# Aircondition.net
KiCad netlist of a schematic drawn in EAGLE
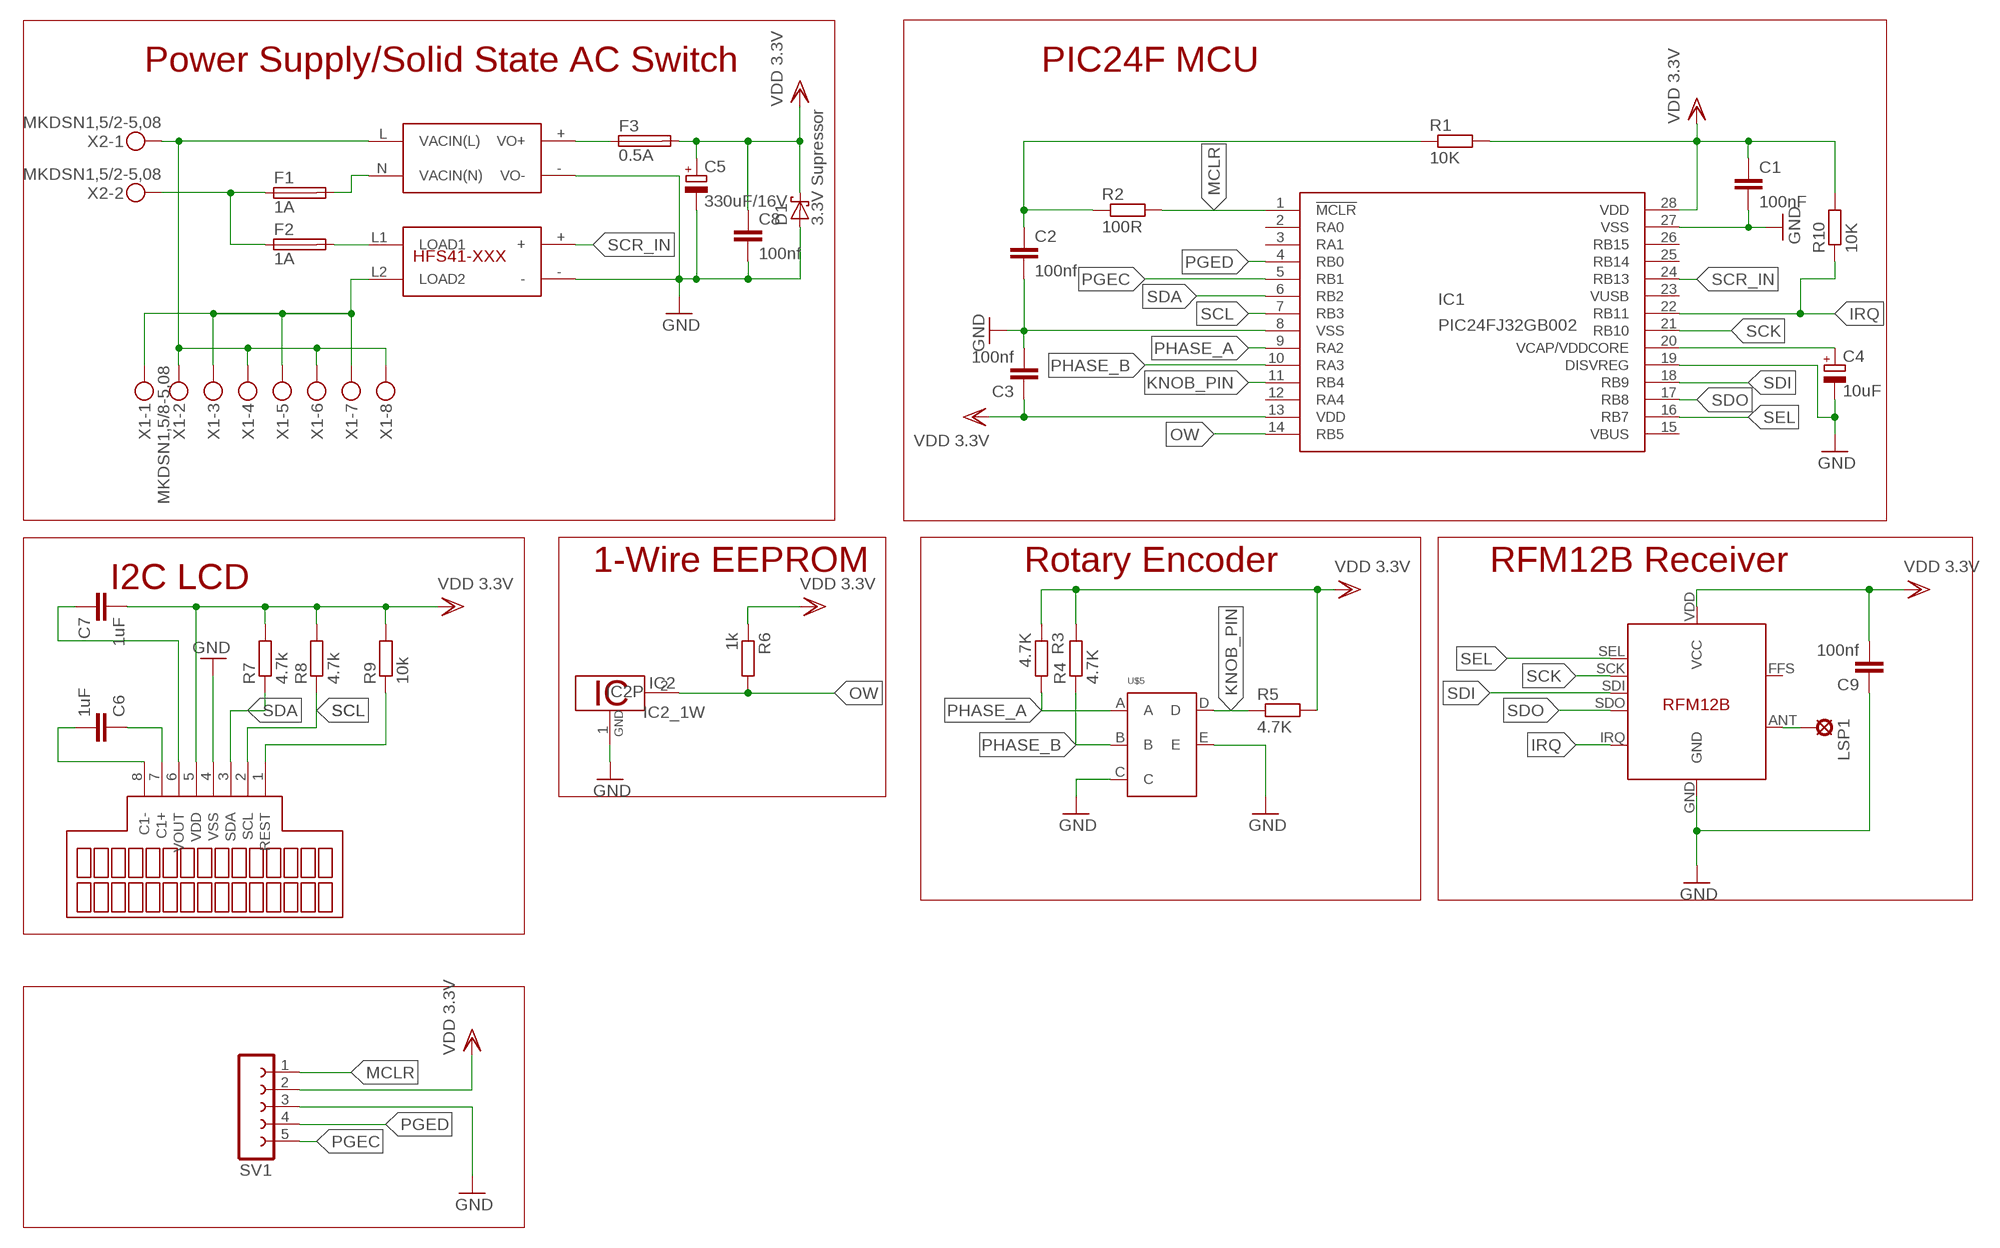
[diagram p0: schematic, sheet 1]

(export (version "E")
  (design (tool "Eeschema 10.0.6"))
  (components
    (comp (ref "C1")
      (value "100nF")
      (footprint "eagle-import:C025-025X050")
      (libsource (lib "eagle-import") (part "C-EU025-025X050"))
    )
    (comp (ref "C2")
      (value "100nf")
      (footprint "eagle-import:C025-025X050")
      (libsource (lib "eagle-import") (part "C-EU025-025X050"))
    )
    (comp (ref "C3")
      (value "100nf")
      (footprint "eagle-import:C102-043X133")
      (libsource (lib "eagle-import") (part "C-EU102-043X133"))
    )
    (comp (ref "C4")
      (value "10uF")
      (footprint "eagle-import:E5-5")
      (libsource (lib "eagle-import") (part "CPOL-EUE5-5"))
    )
    (comp (ref "C5")
      (value "330uF/16V")
      (footprint "eagle-import:E5-10,5")
      (libsource (lib "eagle-import") (part "CPOL-EUE5-10.5"))
    )
    (comp (ref "C6")
      (value "1uF")
      (footprint "eagle-import:C025-025X050")
      (libsource (lib "eagle-import") (part "C-EU025-025X050"))
    )
    (comp (ref "C7")
      (value "1uF")
      (footprint "eagle-import:C025-025X050")
      (libsource (lib "eagle-import") (part "C-EU025-025X050"))
    )
    (comp (ref "C8")
      (value "100nf")
      (footprint "eagle-import:C025-025X050")
      (libsource (lib "eagle-import") (part "C-EU025-025X050"))
    )
    (comp (ref "C9")
      (value "100nf")
      (footprint "eagle-import:C102-043X133")
      (libsource (lib "eagle-import") (part "C-EU102-043X133"))
    )
    (comp (ref "D1")
      (value "3.3V Supressor")
      (footprint "eagle-import:C4111-15")
      (libsource (lib "eagle-import") (part "ICTE5"))
    )
    (comp (ref "F1")
      (value "1A")
      (footprint "eagle-import:SH22,5A")
      (libsource (lib "eagle-import") (part "FUSESH22,5A"))
    )
    (comp (ref "F2")
      (value "1A")
      (footprint "eagle-import:SH22,5A")
      (libsource (lib "eagle-import") (part "FUSESH22,5A"))
    )
    (comp (ref "F3")
      (value "0.5A")
      (footprint "eagle-import:SH22,5A")
      (libsource (lib "eagle-import") (part "FUSESH22,5A"))
    )
    (comp (ref "IC1")
      (value "PIC24FJ32GB002")
      (footprint "eagle-import:DIL28-3")
      (libsource (lib "eagle-import") (part "PIC24FJ32GB002"))
    )
    (comp (ref "IC2")
      (value "DS2431")
      (footprint "eagle-import:TO92-")
      (libsource (lib "eagle-import") (part "DS2431"))
    )
    (comp (ref "LSP1")
      (value "ANT")
      (footprint "eagle-import:LSP10")
      (libsource (lib "eagle-import") (part "LSP10"))
    )
    (comp (ref "R1")
      (value "10K")
      (footprint "eagle-import:0204_5")
      (libsource (lib "eagle-import") (part "R-EU_0204/5"))
    )
    (comp (ref "R2")
      (value "100R")
      (footprint "eagle-import:0204_5")
      (libsource (lib "eagle-import") (part "R-EU_0204/5"))
    )
    (comp (ref "R3")
      (value "4.7K")
      (footprint "eagle-import:0204_7")
      (libsource (lib "eagle-import") (part "R-EU_0204/7"))
    )
    (comp (ref "R4")
      (value "4.7K")
      (footprint "eagle-import:0204_7")
      (libsource (lib "eagle-import") (part "R-EU_0204/7"))
    )
    (comp (ref "R5")
      (value "4.7K")
      (footprint "eagle-import:0204_7")
      (libsource (lib "eagle-import") (part "R-EU_0204/7"))
    )
    (comp (ref "R6")
      (value "1k")
      (footprint "eagle-import:0207_2V")
      (libsource (lib "eagle-import") (part "R-EU_0207/2V"))
    )
    (comp (ref "R7")
      (value "4.7k")
      (footprint "eagle-import:0204_5")
      (libsource (lib "eagle-import") (part "R-EU_0204/5"))
    )
    (comp (ref "R8")
      (value "4.7k")
      (footprint "eagle-import:0204_5")
      (libsource (lib "eagle-import") (part "R-EU_0204/5"))
    )
    (comp (ref "R9")
      (value "10k")
      (footprint "eagle-import:0204_5")
      (libsource (lib "eagle-import") (part "R-EU_0204/5"))
    )
    (comp (ref "R10")
      (value "10K")
      (footprint "eagle-import:0207_10")
      (libsource (lib "eagle-import") (part "R-EU_0207/10"))
    )
    (comp (ref "SV1")
      (value "FE05-1")
      (footprint "eagle-import:FE05-1")
      (libsource (lib "eagle-import") (part "FE05-1"))
    )
    (comp (ref "U$1")
      (value "RAC01-3.3SC")
      (footprint "eagle-import:RAC01-XXSC")
      (libsource (lib "eagle-import") (part "RAC01-3.3SCSTANDARD"))
    )
    (comp (ref "U$2")
      (value "HFS41D-240A5Z-NGSTANDARD")
      (footprint "eagle-import:HFS41-EXPOXY-RESIN")
      (libsource (lib "eagle-import") (part "HFS41D-240A5Z-NGSTANDARD"))
    )
    (comp (ref "U$3")
      (value "NHD-C0216CIZ-FN-FBW-3VSIL8-2.54")
      (footprint "eagle-import:SIL8-2.54")
      (libsource (lib "eagle-import") (part "NHD-C0216CIZ-FN-FBW-3VSIL8-2.54"))
    )
    (comp (ref "U$4")
      (value "RFM12B")
      (footprint "eagle-import:RFM12B")
      (libsource (lib "eagle-import") (part "RFM12B"))
    )
    (comp (ref "U$5")
      (value "ENCODER-E")
      (footprint "eagle-import:ENCODER")
      (libsource (lib "eagle-import") (part "ENCODER-E"))
    )
    (comp (ref "X1")
      (value "MKDSN1,5/8-5,08")
      (footprint "eagle-import:MKDSN1,5_8-5,08")
      (libsource (lib "eagle-import") (part "MKDSN1,5/8-5,08"))
    )
    (comp (ref "X2")
      (value "MKDSN1,5/2-5,08")
      (footprint "eagle-import:MKDSN1,5_2-5,08")
      (libsource (lib "eagle-import") (part "MKDSN1,5/2-5,08"))
    )
  )
  (nets
    (net (code "1") (name "GND") (class "Default")
      (node (ref "C1") (pin "2") (pinfunction "2_2") (pintype "passive"))
      (node (ref "C2") (pin "2") (pinfunction "2_2") (pintype "passive"))
      (node (ref "C3") (pin "2") (pinfunction "2_2") (pintype "passive"))
      (node (ref "C4") (pin "-") (pinfunction "-_-") (pintype "passive"))
      (node (ref "C5") (pin "-") (pinfunction "-_-") (pintype "passive"))
      (node (ref "C8") (pin "2") (pinfunction "2_2") (pintype "passive"))
      (node (ref "C9") (pin "1") (pinfunction "1_1") (pintype "passive"))
      (node (ref "D1") (pin "A") (pinfunction "A_A") (pintype "passive"))
      (node (ref "IC1") (pin "19") (pinfunction "DISVREG_19") (pintype "passive"))
      (node (ref "IC1") (pin "27") (pinfunction "VSS_27") (pintype "power_in"))
      (node (ref "IC1") (pin "8") (pinfunction "VSS_8") (pintype "power_in"))
      (node (ref "IC2") (pin "1") (pinfunction "GND_1") (pintype "power_in"))
      (node (ref "SV1") (pin "3") (pinfunction "3_3") (pintype "passive"))
      (node (ref "U$1") (pin "-") (pinfunction "VO-_-") (pintype "power_in"))
      (node (ref "U$2") (pin "-") (pinfunction "-_-") (pintype "bidirectional"))
      (node (ref "U$3") (pin "4") (pinfunction "VSS_4") (pintype "power_in"))
      (node (ref "U$4") (pin "GND") (pinfunction "GND_GND") (pintype "power_in"))
      (node (ref "U$5") (pin "C") (pinfunction "C_C") (pintype "power_in"))
      (node (ref "U$5") (pin "E") (pinfunction "E_E") (pintype "power_in"))
    )
    (net (code "2") (name "IRQ") (class "Default")
      (node (ref "IC1") (pin "22") (pinfunction "RB11_22") (pintype "input"))
      (node (ref "R10") (pin "1") (pinfunction "1_1") (pintype "passive"))
      (node (ref "U$4") (pin "IRQ") (pinfunction "IRQ_IRQ") (pintype "open_collector"))
    )
    (net (code "3") (name "KNOB_PIN") (class "Default")
      (node (ref "IC1") (pin "11") (pinfunction "RB4_11") (pintype "bidirectional"))
      (node (ref "R5") (pin "1") (pinfunction "1_1") (pintype "passive"))
      (node (ref "U$5") (pin "D") (pinfunction "D_D") (pintype "output"))
    )
    (net (code "4") (name "MCLR") (class "Default")
      (node (ref "IC1") (pin "1") (pinfunction "~{MCLR}_1") (pintype "bidirectional"))
      (node (ref "R2") (pin "2") (pinfunction "2_2") (pintype "passive"))
      (node (ref "SV1") (pin "1") (pinfunction "1_1") (pintype "passive"))
    )
    (net (code "5") (name "Net-(C2-Pad1)") (class "Default")
      (node (ref "C2") (pin "1") (pinfunction "1_1") (pintype "passive"))
      (node (ref "R1") (pin "1") (pinfunction "1_1") (pintype "passive"))
      (node (ref "R2") (pin "1") (pinfunction "1_1") (pintype "passive"))
    )
    (net (code "6") (name "Net-(IC1-VCAP{slash}VDDCORE)") (class "Default")
      (node (ref "C4") (pin "+") (pinfunction "+_+") (pintype "passive"))
      (node (ref "IC1") (pin "20") (pinfunction "VCAP/VDDCORE_20") (pintype "power_in"))
    )
    (net (code "7") (name "Net-(LSP1-PadMP)") (class "Default")
      (node (ref "LSP1") (pin "MP") (pinfunction "MP_MP") (pintype "passive"))
      (node (ref "U$4") (pin "ANT") (pinfunction "ANT_ANT") (pintype "passive"))
    )
    (net (code "8") (name "Net-(U$1-VACIN(L))") (class "Default")
      (node (ref "U$1") (pin "L") (pinfunction "VACIN(L)_L") (pintype "power_in"))
      (node (ref "X1") (pin "2") (pinfunction "KL_2") (pintype "passive"))
      (node (ref "X1") (pin "4") (pinfunction "KL_4") (pintype "passive"))
      (node (ref "X1") (pin "6") (pinfunction "KL_6") (pintype "passive"))
      (node (ref "X1") (pin "8") (pinfunction "KL_8") (pintype "passive"))
      (node (ref "X2") (pin "1") (pinfunction "KL_1") (pintype "passive"))
    )
    (net (code "9") (name "Net-(U$1-VACIN(N))") (class "Default")
      (node (ref "F1") (pin "2") (pinfunction "2_2") (pintype "passive"))
      (node (ref "U$1") (pin "N") (pinfunction "VACIN(N)_N") (pintype "power_in"))
    )
    (net (code "10") (name "Net-(U$1-VO+)") (class "Default")
      (node (ref "F3") (pin "1") (pinfunction "1_1") (pintype "passive"))
      (node (ref "U$1") (pin "+") (pinfunction "VO+_+") (pintype "power_in"))
    )
    (net (code "11") (name "Net-(U$2-LOAD1)") (class "Default")
      (node (ref "F2") (pin "2") (pinfunction "2_2") (pintype "passive"))
      (node (ref "U$2") (pin "L1") (pinfunction "LOAD1_L1") (pintype "bidirectional"))
    )
    (net (code "12") (name "Net-(U$2-LOAD2)") (class "Default")
      (node (ref "U$2") (pin "L2") (pinfunction "LOAD2_L2") (pintype "bidirectional"))
      (node (ref "X1") (pin "1") (pinfunction "KL_1") (pintype "passive"))
      (node (ref "X1") (pin "3") (pinfunction "KL_3") (pintype "passive"))
      (node (ref "X1") (pin "5") (pinfunction "KL_5") (pintype "passive"))
      (node (ref "X1") (pin "7") (pinfunction "KL_7") (pintype "passive"))
    )
    (net (code "13") (name "Net-(U$3-C1+)") (class "Default")
      (node (ref "C6") (pin "1") (pinfunction "1_1") (pintype "passive"))
      (node (ref "U$3") (pin "7") (pinfunction "C1+_7") (pintype "bidirectional"))
    )
    (net (code "14") (name "Net-(U$3-C1-)") (class "Default")
      (node (ref "C6") (pin "2") (pinfunction "2_2") (pintype "passive"))
      (node (ref "U$3") (pin "8") (pinfunction "C1-_8") (pintype "bidirectional"))
    )
    (net (code "15") (name "Net-(U$3-REST)") (class "Default")
      (node (ref "R9") (pin "1") (pinfunction "1_1") (pintype "passive"))
      (node (ref "U$3") (pin "1") (pinfunction "REST_1") (pintype "bidirectional"))
    )
    (net (code "16") (name "Net-(U$3-VOUT)") (class "Default")
      (node (ref "C7") (pin "1") (pinfunction "1_1") (pintype "passive"))
      (node (ref "U$3") (pin "6") (pinfunction "VOUT_6") (pintype "output"))
    )
    (net (code "17") (name "Net-(X2B-KL)") (class "Default")
      (node (ref "F1") (pin "1") (pinfunction "1_1") (pintype "passive"))
      (node (ref "F2") (pin "1") (pinfunction "1_1") (pintype "passive"))
      (node (ref "X2") (pin "2") (pinfunction "KL_2") (pintype "passive"))
    )
    (net (code "18") (name "OW") (class "Default")
      (node (ref "IC1") (pin "14") (pinfunction "RB5_14") (pintype "bidirectional"))
      (node (ref "IC2") (pin "2") (pinfunction "1W_2") (pintype "power_in"))
      (node (ref "R6") (pin "2") (pinfunction "2_2") (pintype "passive"))
    )
    (net (code "19") (name "PGEC") (class "Default")
      (node (ref "IC1") (pin "5") (pinfunction "RB1_5") (pintype "bidirectional"))
      (node (ref "SV1") (pin "5") (pinfunction "5_5") (pintype "passive"))
    )
    (net (code "20") (name "PGED") (class "Default")
      (node (ref "IC1") (pin "4") (pinfunction "RB0_4") (pintype "bidirectional"))
      (node (ref "SV1") (pin "4") (pinfunction "4_4") (pintype "passive"))
    )
    (net (code "21") (name "PHASE_A") (class "Default")
      (node (ref "IC1") (pin "9") (pinfunction "RA2_9") (pintype "bidirectional"))
      (node (ref "R3") (pin "2") (pinfunction "2_2") (pintype "passive"))
      (node (ref "U$5") (pin "A") (pinfunction "A_A") (pintype "output"))
    )
    (net (code "22") (name "PHASE_B") (class "Default")
      (node (ref "IC1") (pin "10") (pinfunction "RA3_10") (pintype "bidirectional"))
      (node (ref "R4") (pin "1") (pinfunction "1_1") (pintype "passive"))
      (node (ref "U$5") (pin "B") (pinfunction "B_B") (pintype "output"))
    )
    (net (code "23") (name "SCK") (class "Default")
      (node (ref "IC1") (pin "21") (pinfunction "RB10_21") (pintype "input"))
      (node (ref "U$4") (pin "SCK") (pinfunction "SCK_SCK") (pintype "input"))
    )
    (net (code "24") (name "SCL") (class "Default")
      (node (ref "IC1") (pin "7") (pinfunction "RB3_7") (pintype "bidirectional"))
      (node (ref "R8") (pin "1") (pinfunction "1_1") (pintype "passive"))
      (node (ref "U$3") (pin "2") (pinfunction "SCL_2") (pintype "bidirectional"))
    )
    (net (code "25") (name "SCR_IN") (class "Default")
      (node (ref "IC1") (pin "24") (pinfunction "RB13_24") (pintype "bidirectional"))
      (node (ref "U$2") (pin "+") (pinfunction "+_+") (pintype "input"))
    )
    (net (code "26") (name "SDA") (class "Default")
      (node (ref "IC1") (pin "6") (pinfunction "RB2_6") (pintype "bidirectional"))
      (node (ref "R7") (pin "1") (pinfunction "1_1") (pintype "passive"))
      (node (ref "U$3") (pin "3") (pinfunction "SDA_3") (pintype "bidirectional"))
    )
    (net (code "27") (name "SDI") (class "Default")
      (node (ref "IC1") (pin "18") (pinfunction "RB9_18") (pintype "output"))
      (node (ref "U$4") (pin "SDI") (pinfunction "SDI_SDI") (pintype "input"))
    )
    (net (code "28") (name "SDO") (class "Default")
      (node (ref "IC1") (pin "17") (pinfunction "RB8_17") (pintype "input"))
      (node (ref "U$4") (pin "SDO") (pinfunction "SDO_SDO") (pintype "output"))
    )
    (net (code "29") (name "SEL") (class "Default")
      (node (ref "IC1") (pin "16") (pinfunction "RB7_16") (pintype "bidirectional"))
      (node (ref "U$4") (pin "SEL") (pinfunction "SEL_SEL") (pintype "input"))
    )
    (net (code "30") (name "VDD 3.3V") (class "Default")
      (node (ref "C1") (pin "1") (pinfunction "1_1") (pintype "passive"))
      (node (ref "C3") (pin "1") (pinfunction "1_1") (pintype "passive"))
      (node (ref "C5") (pin "+") (pinfunction "+_+") (pintype "passive"))
      (node (ref "C7") (pin "2") (pinfunction "2_2") (pintype "passive"))
      (node (ref "C8") (pin "1") (pinfunction "1_1") (pintype "passive"))
      (node (ref "C9") (pin "2") (pinfunction "2_2") (pintype "passive"))
      (node (ref "D1") (pin "C") (pinfunction "C_C") (pintype "passive"))
      (node (ref "F3") (pin "2") (pinfunction "2_2") (pintype "passive"))
      (node (ref "IC1") (pin "13") (pinfunction "VDD_13") (pintype "power_in"))
      (node (ref "IC1") (pin "28") (pinfunction "VDD_28") (pintype "power_in"))
      (node (ref "R1") (pin "2") (pinfunction "2_2") (pintype "passive"))
      (node (ref "R10") (pin "2") (pinfunction "2_2") (pintype "passive"))
      (node (ref "R3") (pin "1") (pinfunction "1_1") (pintype "passive"))
      (node (ref "R4") (pin "2") (pinfunction "2_2") (pintype "passive"))
      (node (ref "R5") (pin "2") (pinfunction "2_2") (pintype "passive"))
      (node (ref "R6") (pin "1") (pinfunction "1_1") (pintype "passive"))
      (node (ref "R7") (pin "2") (pinfunction "2_2") (pintype "passive"))
      (node (ref "R8") (pin "2") (pinfunction "2_2") (pintype "passive"))
      (node (ref "R9") (pin "2") (pinfunction "2_2") (pintype "passive"))
      (node (ref "SV1") (pin "2") (pinfunction "2_2") (pintype "passive"))
      (node (ref "U$3") (pin "5") (pinfunction "VDD_5") (pintype "power_in"))
      (node (ref "U$4") (pin "VDD") (pinfunction "VCC_VDD") (pintype "power_in"))
    )
    (net (code "31") (name "unconnected-(IC1-RA0-Pad2)") (class "Default")
      (node (ref "IC1") (pin "2") (pinfunction "RA0_2") (pintype "bidirectional"))
    )
    (net (code "32") (name "unconnected-(IC1-RA1-Pad3)") (class "Default")
      (node (ref "IC1") (pin "3") (pinfunction "RA1_3") (pintype "bidirectional"))
    )
    (net (code "33") (name "unconnected-(IC1-RA4-Pad12)") (class "Default")
      (node (ref "IC1") (pin "12") (pinfunction "RA4_12") (pintype "bidirectional"))
    )
    (net (code "34") (name "unconnected-(IC1-RB14-Pad25)") (class "Default")
      (node (ref "IC1") (pin "25") (pinfunction "RB14_25") (pintype "bidirectional"))
    )
    (net (code "35") (name "unconnected-(IC1-RB15-Pad26)") (class "Default")
      (node (ref "IC1") (pin "26") (pinfunction "RB15_26") (pintype "bidirectional"))
    )
    (net (code "36") (name "unconnected-(IC1-VBUS-Pad15)") (class "Default")
      (node (ref "IC1") (pin "15") (pinfunction "VBUS_15") (pintype "bidirectional"))
    )
    (net (code "37") (name "unconnected-(IC1-VUSB-Pad23)") (class "Default")
      (node (ref "IC1") (pin "23") (pinfunction "VUSB_23") (pintype "bidirectional"))
    )
    (net (code "38") (name "unconnected-(U$4-PadFFS)") (class "Default")
      (node (ref "U$4") (pin "FFS") (pinfunction "FFS_FFS") (pintype "bidirectional"))
    )
  )
)
